# Power_Unit.net
KiCad netlist of a schematic drawn in Altium Designer
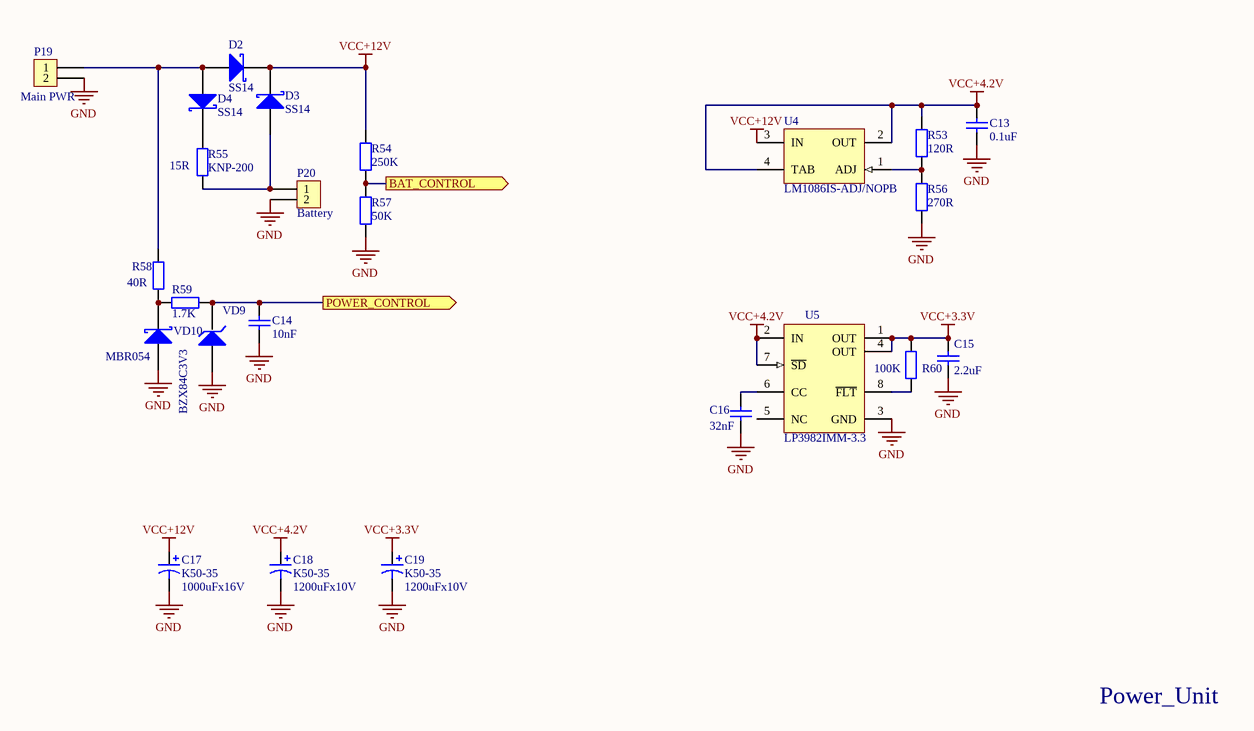
[diagram p0: Power_Unit.SchDoc]

(export (version "E")
  (design (tool "Eeschema 10.0.6"))
  (components
    (comp (ref "C13")
      (value "0.1uF")
      (footprint "C0603")
      (description "Capasitor_SMD_0808/")
      (fields (field (name "Comment") "CAP_SMD"))
      (libsource (lib "NEW") (part "Capasitor_SMD_0805"))
    )
    (comp (ref "C14")
      (value "10nF")
      (footprint "C0603")
      (description "Capasitor_SMD_0808/")
      (fields (field (name "Comment") "0805"))
      (libsource (lib "NEW") (part "Capasitor_SMD_0805"))
    )
    (comp (ref "C15")
      (value "2.2uF")
      (footprint "C0603")
      (description "Capasitor_SMD_0808/")
      (fields (field (name "Comment") "0805"))
      (libsource (lib "NEW") (part "Capasitor_SMD_0805"))
    )
    (comp (ref "C16")
      (value "32nF")
      (footprint "C0603")
      (description "Capasitor_SMD_0808/")
      (fields (field (name "Comment") "0805"))
      (libsource (lib "NEW") (part "Capasitor_SMD_0805"))
    )
    (comp (ref "C17")
      (value "K50-35")
      (footprint "CAP_POL_D10")
      (fields (field (name "ALTIUM_VALUE") "1000uFx16V"))
      (libsource (lib "NEW") (part "Capasitor_pol D10"))
    )
    (comp (ref "C18")
      (value "K50-35")
      (footprint "CAP_POL_D10")
      (fields (field (name "ALTIUM_VALUE") "1200uFx10V"))
      (libsource (lib "NEW") (part "Capasitor_pol D10"))
    )
    (comp (ref "C19")
      (value "K50-35")
      (footprint "CAP_POL_D10")
      (fields (field (name "ALTIUM_VALUE") "1200uFx10V"))
      (libsource (lib "NEW") (part "Capasitor_pol D10"))
    )
    (comp (ref "D2") (value "SS14") (footprint "SMA_Diode") (libsource (lib "NEW") (part "SS14")))
    (comp (ref "D3") (value "SS14") (footprint "SMA_Diode") (libsource (lib "NEW") (part "SS14")))
    (comp (ref "D4") (value "SS14") (footprint "SMA_Diode") (libsource (lib "NEW") (part "SS14")))
    (comp (ref "P19") (value "Main PWR") (footprint "WF 02M") (libsource (lib "") (part "WF 02M_1")))
    (comp (ref "P20") (value "Battery") (footprint "WF 02M") (libsource (lib "NEW") (part "WF 02M")))
    (comp (ref "R53")
      (value "120R")
      (footprint "C0805")
      (description "Resistor")
      (fields (field (name "Comment") "RES"))
      (libsource (lib "NEW") (part "RES"))
    )
    (comp (ref "R54")
      (value "250K")
      (footprint "C0603")
      (description "Resistor")
      (fields (field (name "Comment") "RES_SMD"))
      (libsource (lib "NEW") (part "RES"))
    )
    (comp (ref "R55")
      (value "KNP-200")
      (footprint "Resistor KNP-200")
      (fields (field (name "ALTIUM_VALUE") "15R"))
      (libsource (lib "NEW") (part "Resistor 2W"))
    )
    (comp (ref "R56")
      (value "270R")
      (footprint "C0805")
      (description "Resistor")
      (fields (field (name "Comment") "RES"))
      (libsource (lib "NEW") (part "RES"))
    )
    (comp (ref "R57")
      (value "50K")
      (footprint "C0603")
      (description "Resistor")
      (fields (field (name "Comment") "RES_SMD"))
      (libsource (lib "NEW") (part "RES"))
    )
    (comp (ref "R58")
      (value "40R")
      (footprint "C0805")
      (description "Resistor")
      (fields (field (name "Comment") "RES"))
      (libsource (lib "NEW") (part "RES"))
    )
    (comp (ref "R59")
      (value "1.7K")
      (footprint "C0805")
      (description "Resistor")
      (fields (field (name "Comment") "RES"))
      (libsource (lib "") (part "RES_1"))
    )
    (comp (ref "R60")
      (value "100K")
      (footprint "C0603")
      (description "Resistor")
      (fields (field (name "Comment") "RES"))
      (libsource (lib "NEW") (part "RES"))
    )
    (comp (ref "U4")
      (value "LM1086IS-ADJ/NOPB")
      (footprint "TS3B_N")
      (description "1.5A Low Dropout Positive Regulators, 3-pin TO-263, Pb-Free")
      (fields
        (field (name "MANUFACTURER") "National Semiconductor")
        (field (name "PUBLISHER") "Altium Limited")
      )
      (libsource (lib "NSC LDO") (part "LM1086IS-ADJ/NOPB"))
    )
    (comp (ref "U5")
      (value "LP3982IMM-3.3")
      (footprint "MUA08A_N")
      (description "Micropower, Ultra Low-Dropout, Low-Noise, 300mA CMOS Regulator, 8-pin Mini SOIC")
      (fields
        (field (name "MANUFACTURER") "National Semiconductor")
        (field (name "PUBLISHER") "Altium Limited")
      )
      (libsource (lib "NSC LDO") (part "LP3982IMM-3.3"))
    )
    (comp (ref "VD9")
      (value "BZX84C3V3")
      (footprint "SOT23")
      (description "BZX84C")
      (libsource (lib "NEW") (part "BZX84C"))
    )
    (comp (ref "VD10") (value "MBR054") (footprint "SOD-123") (libsource (lib "NEW") (part "MBR054")))
  )
  (nets
    (net (code "1") (name "/BAT_CONTROL") (class "Default")
      (node (ref "R54") (pin "1") (pinfunction "1_1") (pintype "passive"))
      (node (ref "R57") (pin "2") (pinfunction "2_2") (pintype "passive"))
    )
    (net (code "2") (name "/POWER_CONTROL") (class "Default")
      (node (ref "C14") (pin "1") (pinfunction "1_1") (pintype "passive"))
      (node (ref "R59") (pin "2") (pinfunction "2_2") (pintype "passive"))
      (node (ref "VD9") (pin "3") (pinfunction "K_3") (pintype "passive"))
    )
    (net (code "3") (name "GND") (class "Default")
      (node (ref "C13") (pin "2") (pinfunction "2_2") (pintype "passive"))
      (node (ref "C14") (pin "2") (pinfunction "2_2") (pintype "passive"))
      (node (ref "C15") (pin "2") (pinfunction "2_2") (pintype "passive"))
      (node (ref "C16") (pin "2") (pinfunction "2_2") (pintype "passive"))
      (node (ref "C17") (pin "2") (pinfunction "2_2") (pintype "passive"))
      (node (ref "C18") (pin "2") (pinfunction "2_2") (pintype "passive"))
      (node (ref "C19") (pin "2") (pinfunction "2_2") (pintype "passive"))
      (node (ref "P19") (pin "2") (pinfunction "2_2") (pintype "passive"))
      (node (ref "P20") (pin "2") (pinfunction "2_2") (pintype "passive"))
      (node (ref "R56") (pin "1") (pinfunction "1_1") (pintype "passive"))
      (node (ref "R57") (pin "1") (pinfunction "1_1") (pintype "passive"))
      (node (ref "U5") (pin "3") (pinfunction "GND_3") (pintype "power_in"))
      (node (ref "VD10") (pin "2") (pinfunction "A_2") (pintype "passive"))
      (node (ref "VD9") (pin "1") (pinfunction "A_1") (pintype "passive"))
    )
    (net (code "4") (name "Net-(D2-A)") (class "Default")
      (node (ref "D2") (pin "2") (pinfunction "A_2") (pintype "passive"))
      (node (ref "D4") (pin "2") (pinfunction "A_2") (pintype "passive"))
      (node (ref "P19") (pin "1") (pinfunction "1_1") (pintype "passive"))
      (node (ref "R58") (pin "2") (pinfunction "2_2") (pintype "passive"))
    )
    (net (code "5") (name "Net-(D3-A)") (class "Default")
      (node (ref "D3") (pin "2") (pinfunction "A_2") (pintype "passive"))
      (node (ref "P20") (pin "1") (pinfunction "1_1") (pintype "passive"))
      (node (ref "R55") (pin "1") (pinfunction "1_1") (pintype "passive"))
    )
    (net (code "6") (name "Net-(D4-K)") (class "Default")
      (node (ref "D4") (pin "1") (pinfunction "K_1") (pintype "passive"))
      (node (ref "R55") (pin "2") (pinfunction "2_2") (pintype "passive"))
    )
    (net (code "7") (name "Net-(U4-ADJ)") (class "Default")
      (node (ref "R53") (pin "1") (pinfunction "1_1") (pintype "passive"))
      (node (ref "R56") (pin "2") (pinfunction "2_2") (pintype "passive"))
      (node (ref "U4") (pin "1") (pinfunction "ADJ_1") (pintype "input"))
    )
    (net (code "8") (name "Net-(U5-CC)") (class "Default")
      (node (ref "C16") (pin "1") (pinfunction "1_1") (pintype "passive"))
      (node (ref "U5") (pin "6") (pinfunction "CC_6") (pintype "passive"))
    )
    (net (code "9") (name "Net-(U5-~{FLT})") (class "Default")
      (node (ref "R60") (pin "1") (pinfunction "1_1") (pintype "passive"))
      (node (ref "U5") (pin "8") (pinfunction "~{FLT}_8") (pintype "open_collector"))
    )
    (net (code "10") (name "Net-(VD10-K)") (class "Default")
      (node (ref "R58") (pin "1") (pinfunction "1_1") (pintype "passive"))
      (node (ref "R59") (pin "1") (pinfunction "1_1") (pintype "passive"))
      (node (ref "VD10") (pin "1") (pinfunction "K_1") (pintype "passive"))
    )
    (net (code "11") (name "VCC+3.3V") (class "Default")
      (node (ref "C15") (pin "1") (pinfunction "1_1") (pintype "passive"))
      (node (ref "C19") (pin "1") (pinfunction "1_1") (pintype "passive"))
      (node (ref "R60") (pin "2") (pinfunction "2_2") (pintype "passive"))
      (node (ref "U5") (pin "1") (pinfunction "OUT_1") (pintype "power_in"))
      (node (ref "U5") (pin "4") (pinfunction "OUT_4") (pintype "power_in"))
    )
    (net (code "12") (name "VCC+4.2V") (class "Default")
      (node (ref "C13") (pin "1") (pinfunction "1_1") (pintype "passive"))
      (node (ref "C18") (pin "1") (pinfunction "1_1") (pintype "passive"))
      (node (ref "R53") (pin "2") (pinfunction "2_2") (pintype "passive"))
      (node (ref "U4") (pin "2") (pinfunction "OUT_2") (pintype "power_in"))
      (node (ref "U4") (pin "4") (pinfunction "TAB_4") (pintype "power_in"))
      (node (ref "U5") (pin "2") (pinfunction "IN_2") (pintype "power_in"))
      (node (ref "U5") (pin "7") (pinfunction "~{SD}_7") (pintype "input"))
    )
    (net (code "13") (name "VCC+12V") (class "Default")
      (node (ref "C17") (pin "1") (pinfunction "1_1") (pintype "passive"))
      (node (ref "D2") (pin "1") (pinfunction "K_1") (pintype "passive"))
      (node (ref "D3") (pin "1") (pinfunction "K_1") (pintype "passive"))
      (node (ref "R54") (pin "2") (pinfunction "2_2") (pintype "passive"))
      (node (ref "U4") (pin "3") (pinfunction "IN_3") (pintype "power_in"))
    )
    (net (code "14") (name "unconnected-(U5-NC-Pad5)") (class "Default")
      (node (ref "U5") (pin "5") (pinfunction "NC_5") (pintype "passive"))
    )
    (net (code "15") (name "unconnected-(VD9-Pad2)") (class "Default")
      (node (ref "VD9") (pin "2") (pintype "passive"))
    )
  )
)
